# Arduino-DIP.net
KiCad netlist of a schematic drawn in EAGLE
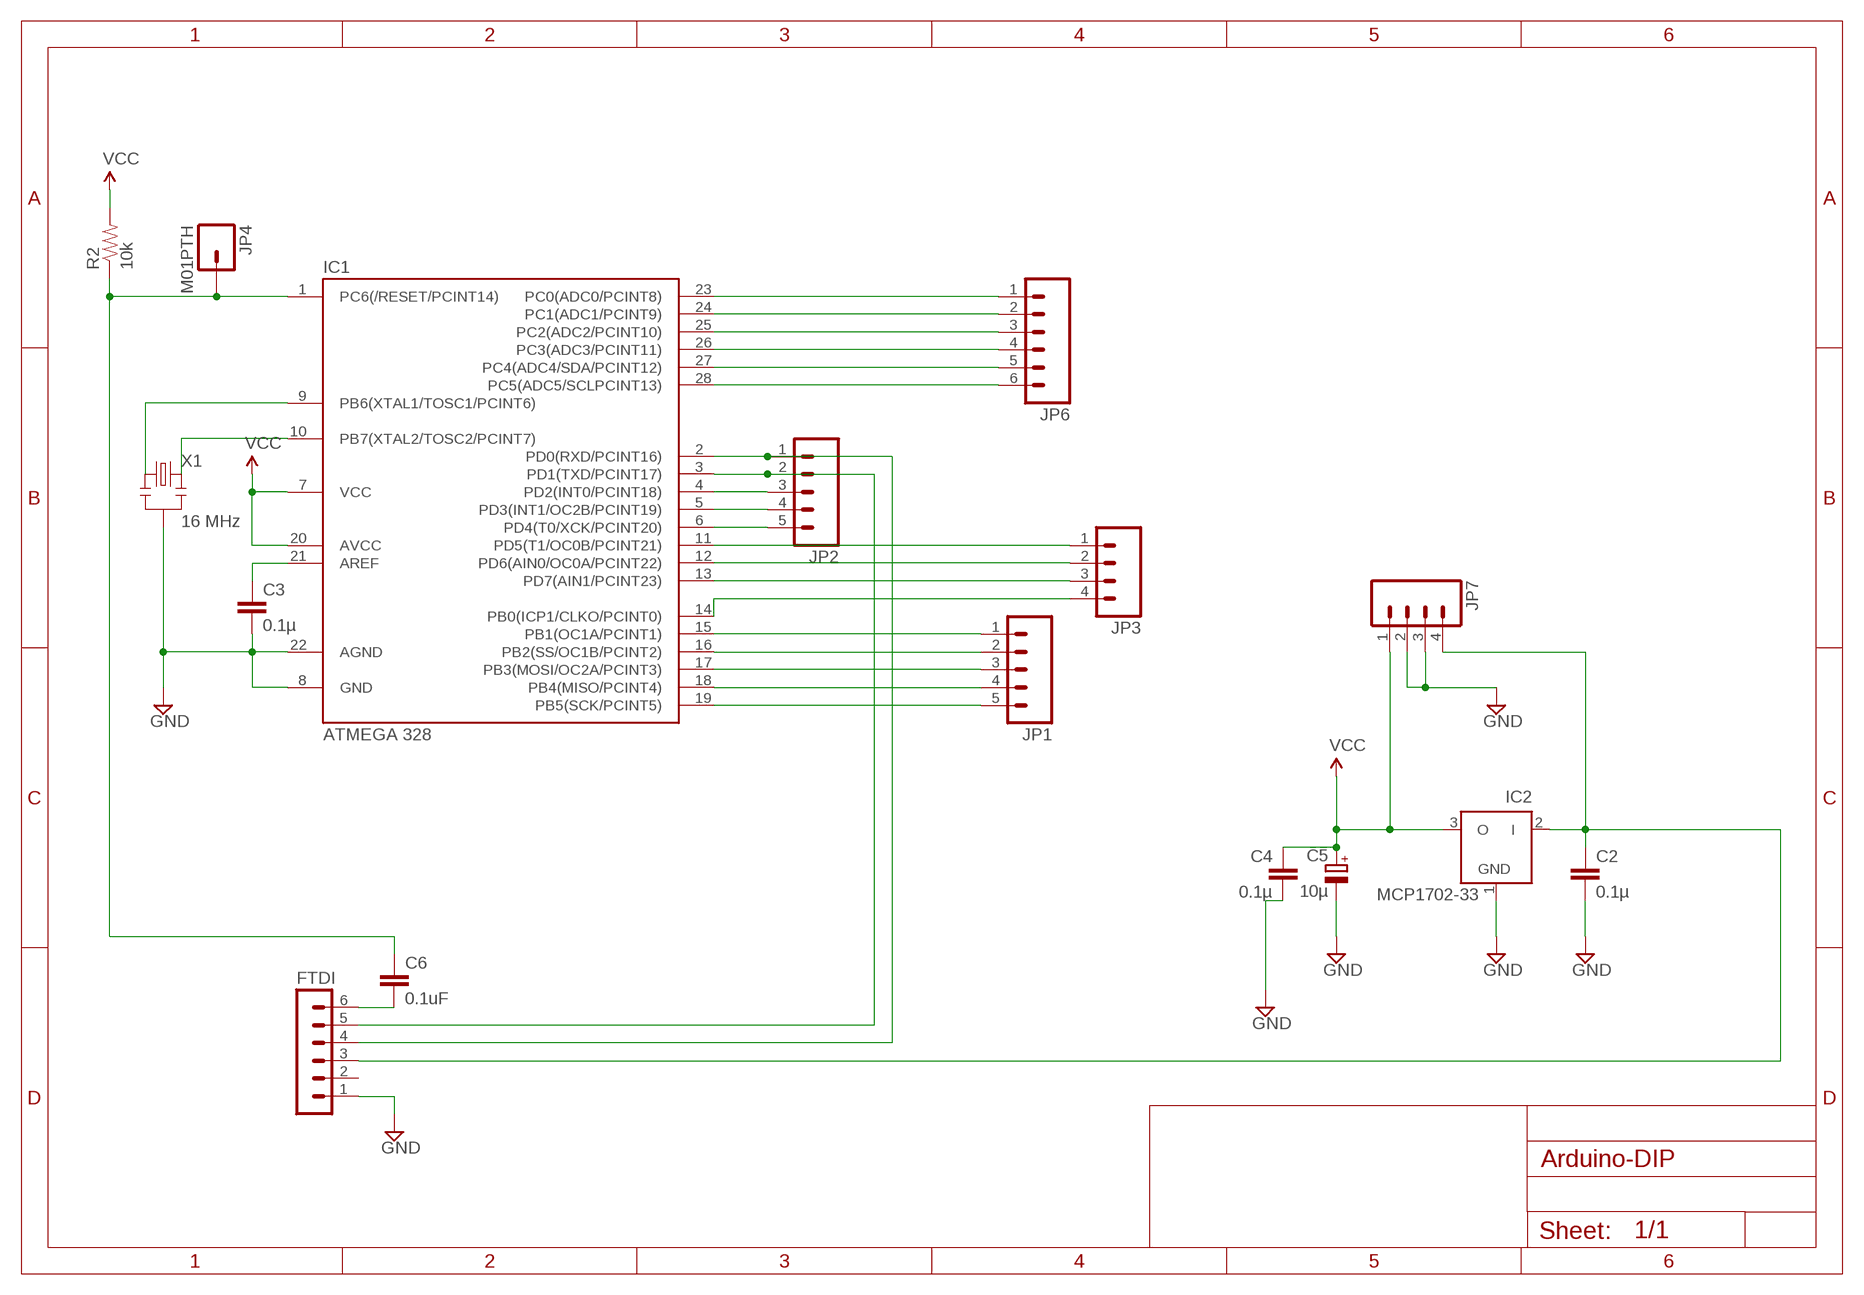
[diagram p0: schematic, sheet 1]

(export (version "E")
  (design (tool "Eeschema 10.0.6"))
  (components
    (comp (ref "C2")
      (value "0.1µ")
      (footprint "eagle-import:C025-024X044")
      (libsource (lib "eagle-import") (part "C-EU025-024X044"))
    )
    (comp (ref "C3")
      (value "0.1µ")
      (footprint "eagle-import:C025-024X044")
      (libsource (lib "eagle-import") (part "C-EU025-024X044"))
    )
    (comp (ref "C4")
      (value "0.1µ")
      (footprint "eagle-import:C025-024X044")
      (libsource (lib "eagle-import") (part "C-EU025-024X044"))
    )
    (comp (ref "C5")
      (value "10µ")
      (footprint "eagle-import:E1,8-4")
      (libsource (lib "eagle-import") (part "CPOL-EUE1.8-4"))
    )
    (comp (ref "C6")
      (value "0.1uF")
      (footprint "eagle-import:CAP-PTH-5MM")
      (libsource (lib "eagle-import") (part "CAPPTH1"))
    )
    (comp (ref "FTDI")
      (value "FTDI")
      (footprint "eagle-import:MA06-1")
      (libsource (lib "eagle-import") (part "MA06-1"))
    )
    (comp (ref "IC1")
      (value "ATMEGA 328")
      (footprint "eagle-import:DIL28-3")
      (libsource (lib "eagle-import") (part "ATMEGA48/88/168-PU"))
    )
    (comp (ref "IC2")
      (value "MCP1702-33")
      (footprint "eagle-import:TO92")
      (libsource (lib "eagle-import") (part "MCP1702Z"))
    )
    (comp (ref "JP1")
      (value "M05PTH")
      (footprint "eagle-import:1X05")
      (libsource (lib "eagle-import") (part "M05PTH"))
    )
    (comp (ref "JP2")
      (value "M05PTH")
      (footprint "eagle-import:1X05")
      (libsource (lib "eagle-import") (part "M05PTH"))
    )
    (comp (ref "JP3")
      (value "M04PTH")
      (footprint "eagle-import:1X04")
      (libsource (lib "eagle-import") (part "M04PTH"))
    )
    (comp (ref "JP4")
      (value "M01PTH")
      (footprint "eagle-import:1X01")
      (libsource (lib "eagle-import") (part "M01PTH"))
    )
    (comp (ref "JP6")
      (value "M06NO_SILK")
      (footprint "eagle-import:1X06_NO_SILK")
      (libsource (lib "eagle-import") (part "M06NO_SILK"))
    )
    (comp (ref "JP7")
      (value "M04PTH")
      (footprint "eagle-import:1X04")
      (libsource (lib "eagle-import") (part "M04PTH"))
    )
    (comp (ref "R2")
      (value "10k")
      (footprint "eagle-import:1_6W-RES")
      (libsource (lib "eagle-import") (part "RESISTORPTH-1/6W"))
    )
    (comp (ref "X1")
      (value "16 MHz")
      (footprint "eagle-import:RESONATOR-PTH")
      (libsource (lib "eagle-import") (part "RESONATORPTH"))
    )
  )
  (nets
    (net (code "1") (name "GND") (class "Default")
      (node (ref "C2") (pin "2") (pinfunction "2_2") (pintype "passive"))
      (node (ref "C3") (pin "2") (pinfunction "2_2") (pintype "passive"))
      (node (ref "C4") (pin "2") (pinfunction "2_2") (pintype "passive"))
      (node (ref "C5") (pin "-") (pinfunction "-_-") (pintype "passive"))
      (node (ref "FTDI") (pin "1") (pinfunction "1_1") (pintype "passive"))
      (node (ref "IC1") (pin "22") (pinfunction "AGND_22") (pintype "power_in"))
      (node (ref "IC1") (pin "8") (pinfunction "GND_8") (pintype "power_in"))
      (node (ref "IC2") (pin "1") (pinfunction "GND_1") (pintype "power_in"))
      (node (ref "JP7") (pin "2") (pinfunction "2_2") (pintype "passive"))
      (node (ref "JP7") (pin "3") (pinfunction "3_3") (pintype "passive"))
      (node (ref "X1") (pin "2") (pinfunction "2_2") (pintype "passive"))
    )
    (net (code "2") (name "Net-(C6-Pad2)") (class "Default")
      (node (ref "C6") (pin "2") (pinfunction "2_2") (pintype "passive"))
      (node (ref "FTDI") (pin "6") (pinfunction "6_6") (pintype "passive"))
    )
    (net (code "3") (name "Net-(IC1-AREF)") (class "Default")
      (node (ref "C3") (pin "1") (pinfunction "1_1") (pintype "passive"))
      (node (ref "IC1") (pin "21") (pinfunction "AREF_21") (pintype "passive"))
    )
    (net (code "4") (name "Net-(IC1-PB0(ICP1{slash}CLKO{slash}PCINT0))") (class "Default")
      (node (ref "IC1") (pin "14") (pinfunction "PB0(ICP1/CLKO/PCINT0)_14") (pintype "bidirectional"))
      (node (ref "JP3") (pin "4") (pinfunction "4_4") (pintype "passive"))
    )
    (net (code "5") (name "Net-(IC1-PB1(OC1A{slash}PCINT1))") (class "Default")
      (node (ref "IC1") (pin "15") (pinfunction "PB1(OC1A/PCINT1)_15") (pintype "bidirectional"))
      (node (ref "JP1") (pin "1") (pinfunction "1_1") (pintype "passive"))
    )
    (net (code "6") (name "Net-(IC1-PB2(SS{slash}OC1B{slash}PCINT2))") (class "Default")
      (node (ref "IC1") (pin "16") (pinfunction "PB2(SS/OC1B/PCINT2)_16") (pintype "bidirectional"))
      (node (ref "JP1") (pin "2") (pinfunction "2_2") (pintype "passive"))
    )
    (net (code "7") (name "Net-(IC1-PB3(MOSI{slash}OC2A{slash}PCINT3))") (class "Default")
      (node (ref "IC1") (pin "17") (pinfunction "PB3(MOSI/OC2A/PCINT3)_17") (pintype "bidirectional"))
      (node (ref "JP1") (pin "3") (pinfunction "3_3") (pintype "passive"))
    )
    (net (code "8") (name "Net-(IC1-PB4(MISO{slash}PCINT4))") (class "Default")
      (node (ref "IC1") (pin "18") (pinfunction "PB4(MISO/PCINT4)_18") (pintype "bidirectional"))
      (node (ref "JP1") (pin "4") (pinfunction "4_4") (pintype "passive"))
    )
    (net (code "9") (name "Net-(IC1-PB5(SCK{slash}PCINT5))") (class "Default")
      (node (ref "IC1") (pin "19") (pinfunction "PB5(SCK/PCINT5)_19") (pintype "bidirectional"))
      (node (ref "JP1") (pin "5") (pinfunction "5_5") (pintype "passive"))
    )
    (net (code "10") (name "Net-(IC1-PB6(XTAL1{slash}TOSC1{slash}PCINT6))") (class "Default")
      (node (ref "IC1") (pin "9") (pinfunction "PB6(XTAL1/TOSC1/PCINT6)_9") (pintype "bidirectional"))
      (node (ref "X1") (pin "1") (pinfunction "1_1") (pintype "passive"))
    )
    (net (code "11") (name "Net-(IC1-PB7(XTAL2{slash}TOSC2{slash}PCINT7))") (class "Default")
      (node (ref "IC1") (pin "10") (pinfunction "PB7(XTAL2/TOSC2/PCINT7)_10") (pintype "bidirectional"))
      (node (ref "X1") (pin "3") (pinfunction "3_3") (pintype "passive"))
    )
    (net (code "12") (name "Net-(IC1-PC0(ADC0{slash}PCINT8))") (class "Default")
      (node (ref "IC1") (pin "23") (pinfunction "PC0(ADC0/PCINT8)_23") (pintype "bidirectional"))
      (node (ref "JP6") (pin "1") (pinfunction "1_1") (pintype "passive"))
    )
    (net (code "13") (name "Net-(IC1-PC1(ADC1{slash}PCINT9))") (class "Default")
      (node (ref "IC1") (pin "24") (pinfunction "PC1(ADC1/PCINT9)_24") (pintype "bidirectional"))
      (node (ref "JP6") (pin "2") (pinfunction "2_2") (pintype "passive"))
    )
    (net (code "14") (name "Net-(IC1-PC2(ADC2{slash}PCINT10))") (class "Default")
      (node (ref "IC1") (pin "25") (pinfunction "PC2(ADC2/PCINT10)_25") (pintype "bidirectional"))
      (node (ref "JP6") (pin "3") (pinfunction "3_3") (pintype "passive"))
    )
    (net (code "15") (name "Net-(IC1-PC3(ADC3{slash}PCINT11))") (class "Default")
      (node (ref "IC1") (pin "26") (pinfunction "PC3(ADC3/PCINT11)_26") (pintype "bidirectional"))
      (node (ref "JP6") (pin "4") (pinfunction "4_4") (pintype "passive"))
    )
    (net (code "16") (name "Net-(IC1-PC4(ADC4{slash}SDA{slash}PCINT12))") (class "Default")
      (node (ref "IC1") (pin "27") (pinfunction "PC4(ADC4/SDA/PCINT12)_27") (pintype "bidirectional"))
      (node (ref "JP6") (pin "5") (pinfunction "5_5") (pintype "passive"))
    )
    (net (code "17") (name "Net-(IC1-PC5(ADC5{slash}SCLPCINT13))") (class "Default")
      (node (ref "IC1") (pin "28") (pinfunction "PC5(ADC5/SCLPCINT13)_28") (pintype "bidirectional"))
      (node (ref "JP6") (pin "6") (pinfunction "6_6") (pintype "passive"))
    )
    (net (code "18") (name "Net-(IC1-PC6({slash}RESET{slash}PCINT14))") (class "Default")
      (node (ref "C6") (pin "1") (pinfunction "1_1") (pintype "passive"))
      (node (ref "IC1") (pin "1") (pinfunction "PC6(/RESET/PCINT14)_1") (pintype "bidirectional"))
      (node (ref "JP4") (pin "1") (pinfunction "1_1") (pintype "passive"))
      (node (ref "R2") (pin "1") (pinfunction "1_1") (pintype "passive"))
    )
    (net (code "19") (name "Net-(IC1-PD0(RXD{slash}PCINT16))") (class "Default")
      (node (ref "FTDI") (pin "4") (pinfunction "4_4") (pintype "passive"))
      (node (ref "IC1") (pin "2") (pinfunction "PD0(RXD/PCINT16)_2") (pintype "bidirectional"))
      (node (ref "JP2") (pin "1") (pinfunction "1_1") (pintype "passive"))
    )
    (net (code "20") (name "Net-(IC1-PD1(TXD{slash}PCINT17))") (class "Default")
      (node (ref "FTDI") (pin "5") (pinfunction "5_5") (pintype "passive"))
      (node (ref "IC1") (pin "3") (pinfunction "PD1(TXD/PCINT17)_3") (pintype "bidirectional"))
      (node (ref "JP2") (pin "2") (pinfunction "2_2") (pintype "passive"))
    )
    (net (code "21") (name "Net-(IC1-PD2(INT0{slash}PCINT18))") (class "Default")
      (node (ref "IC1") (pin "4") (pinfunction "PD2(INT0/PCINT18)_4") (pintype "bidirectional"))
      (node (ref "JP2") (pin "3") (pinfunction "3_3") (pintype "passive"))
    )
    (net (code "22") (name "Net-(IC1-PD3(INT1{slash}OC2B{slash}PCINT19))") (class "Default")
      (node (ref "IC1") (pin "5") (pinfunction "PD3(INT1/OC2B/PCINT19)_5") (pintype "bidirectional"))
      (node (ref "JP2") (pin "4") (pinfunction "4_4") (pintype "passive"))
    )
    (net (code "23") (name "Net-(IC1-PD4(T0{slash}XCK{slash}PCINT20))") (class "Default")
      (node (ref "IC1") (pin "6") (pinfunction "PD4(T0/XCK/PCINT20)_6") (pintype "bidirectional"))
      (node (ref "JP2") (pin "5") (pinfunction "5_5") (pintype "passive"))
    )
    (net (code "24") (name "Net-(IC1-PD5(T1{slash}OC0B{slash}PCINT21))") (class "Default")
      (node (ref "IC1") (pin "11") (pinfunction "PD5(T1/OC0B/PCINT21)_11") (pintype "bidirectional"))
      (node (ref "JP3") (pin "1") (pinfunction "1_1") (pintype "passive"))
    )
    (net (code "25") (name "Net-(IC1-PD6(AIN0{slash}OC0A{slash}PCINT22))") (class "Default")
      (node (ref "IC1") (pin "12") (pinfunction "PD6(AIN0/OC0A/PCINT22)_12") (pintype "bidirectional"))
      (node (ref "JP3") (pin "2") (pinfunction "2_2") (pintype "passive"))
    )
    (net (code "26") (name "Net-(IC1-PD7(AIN1{slash}PCINT23))") (class "Default")
      (node (ref "IC1") (pin "13") (pinfunction "PD7(AIN1/PCINT23)_13") (pintype "bidirectional"))
      (node (ref "JP3") (pin "3") (pinfunction "3_3") (pintype "passive"))
    )
    (net (code "27") (name "Net-(IC2-I)") (class "Default")
      (node (ref "C2") (pin "1") (pinfunction "1_1") (pintype "passive"))
      (node (ref "FTDI") (pin "3") (pinfunction "3_3") (pintype "passive"))
      (node (ref "IC2") (pin "2") (pinfunction "I_2") (pintype "input"))
      (node (ref "JP7") (pin "4") (pinfunction "4_4") (pintype "passive"))
    )
    (net (code "28") (name "VCC") (class "Default")
      (node (ref "C4") (pin "1") (pinfunction "1_1") (pintype "passive"))
      (node (ref "C5") (pin "+") (pinfunction "+_+") (pintype "passive"))
      (node (ref "IC1") (pin "20") (pinfunction "AVCC_20") (pintype "passive"))
      (node (ref "IC1") (pin "7") (pinfunction "VCC_7") (pintype "power_in"))
      (node (ref "IC2") (pin "3") (pinfunction "O_3") (pintype "input"))
      (node (ref "JP7") (pin "1") (pinfunction "1_1") (pintype "passive"))
      (node (ref "R2") (pin "2") (pinfunction "2_2") (pintype "passive"))
    )
    (net (code "29") (name "unconnected-(FTDI-Pad2)") (class "Default")
      (node (ref "FTDI") (pin "2") (pinfunction "2_2") (pintype "passive"))
    )
  )
)
